# Copy_ofAirScout_SchematicsV2_0.net
KiCad netlist of a schematic drawn in Altium Designer
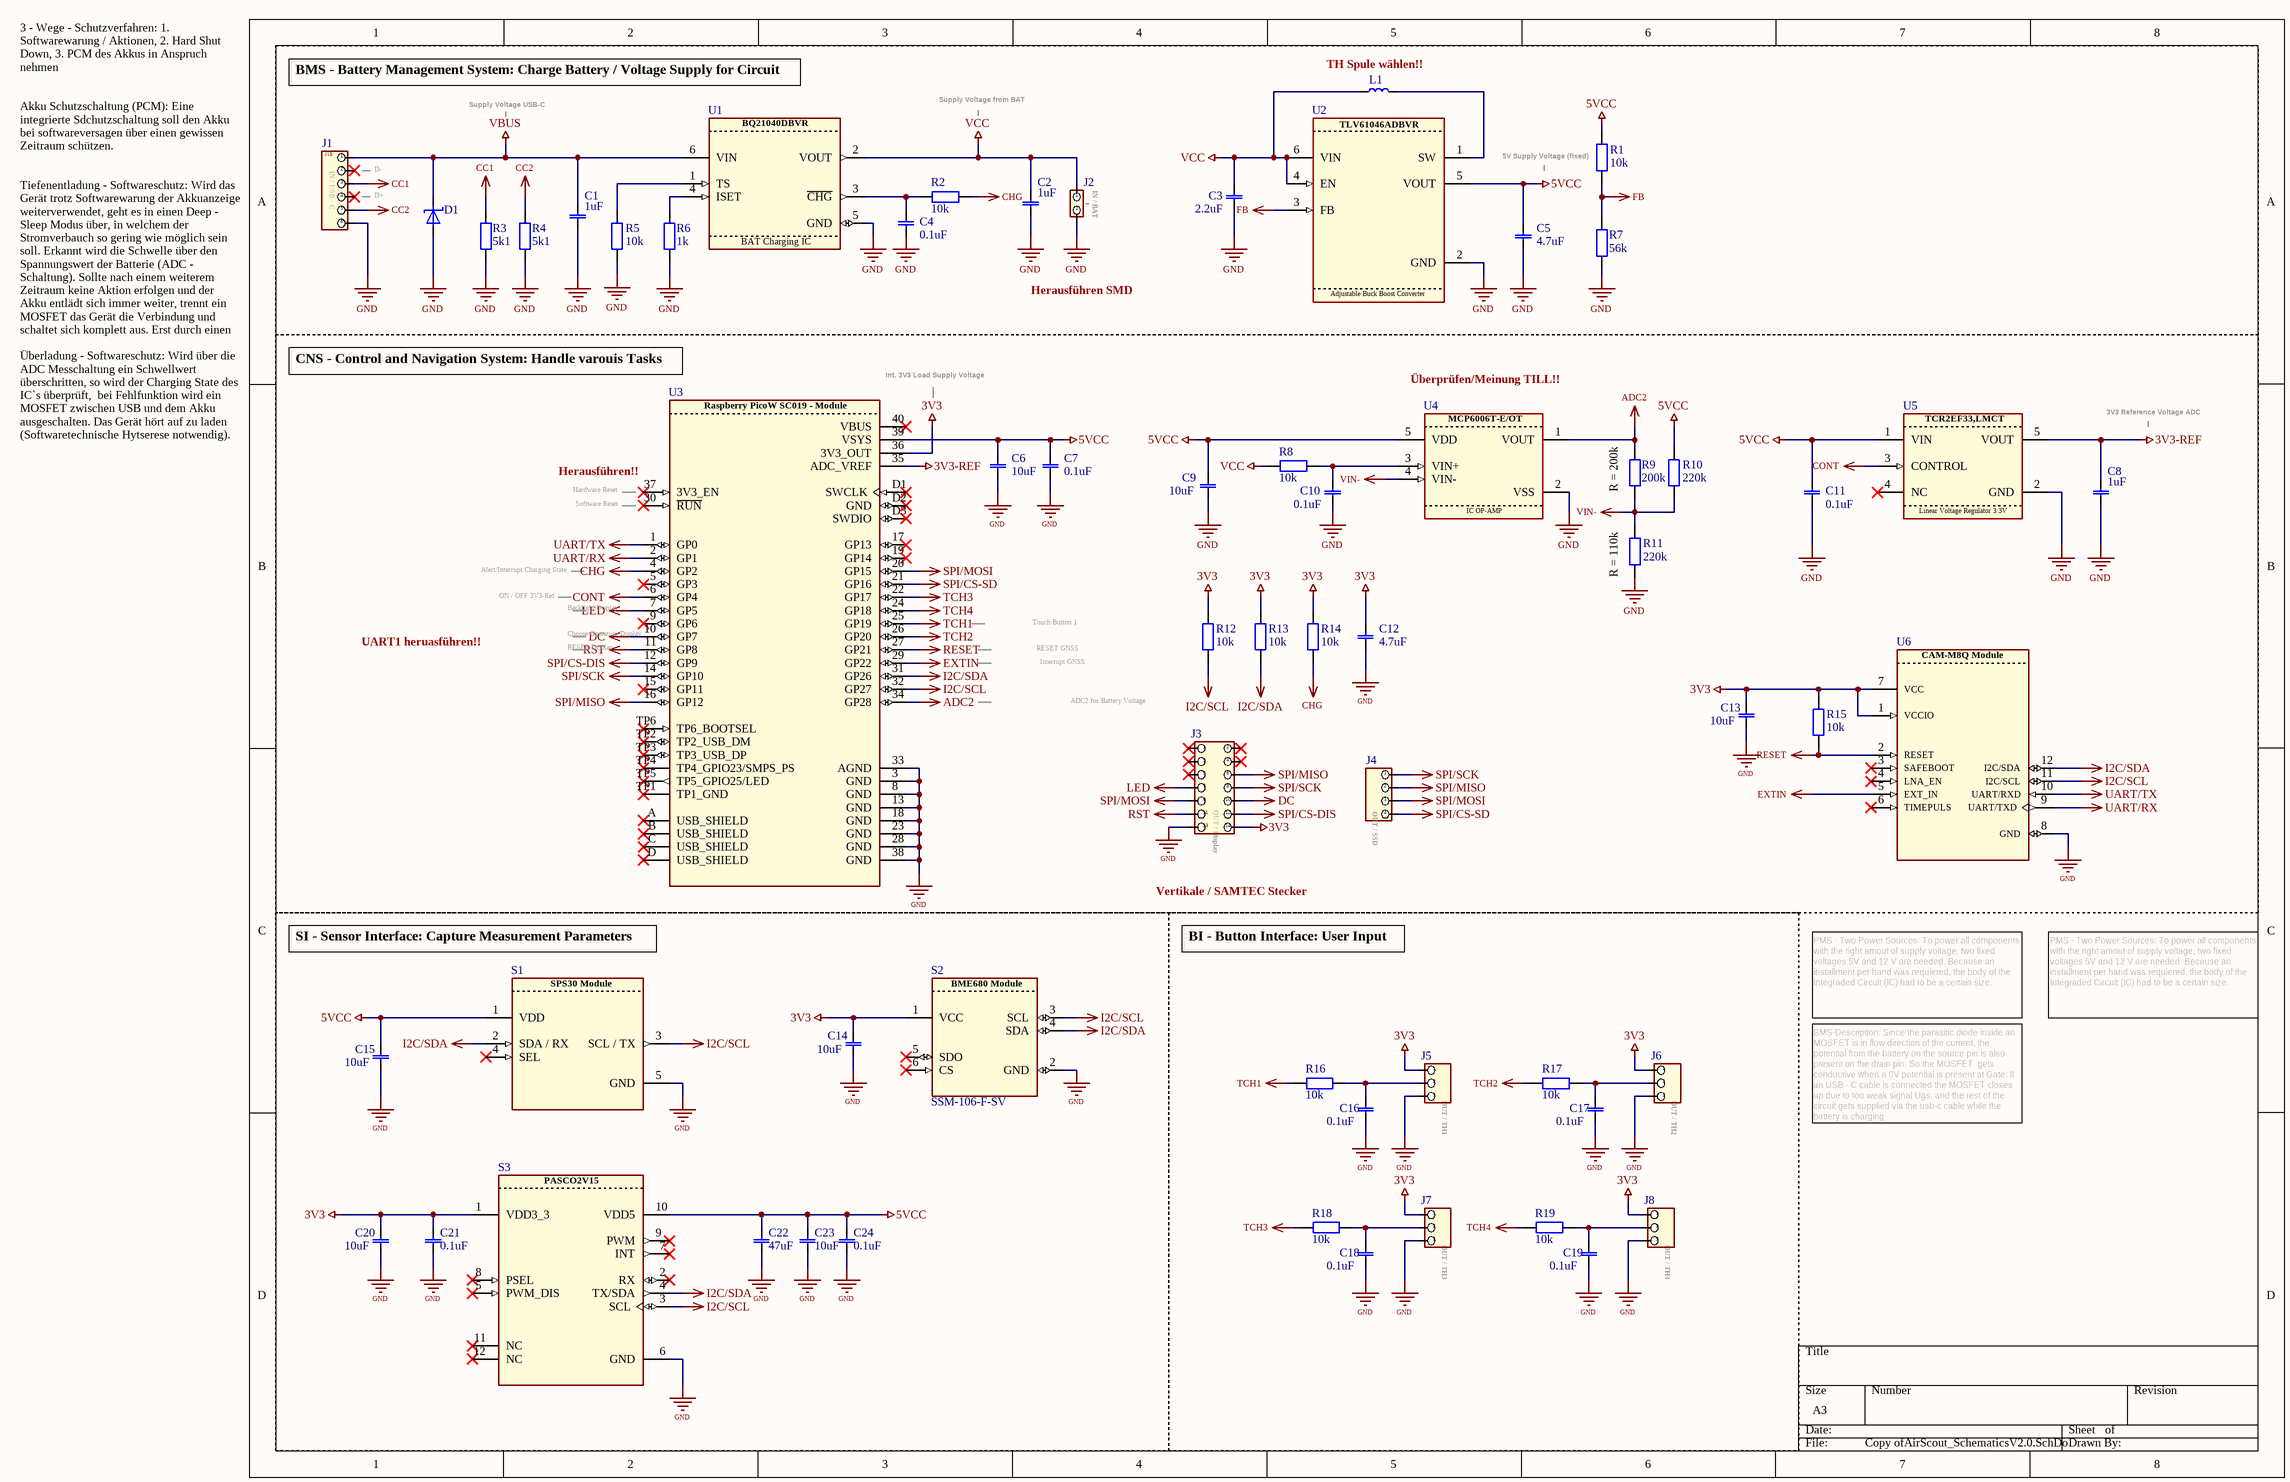
[diagram p0: Copy ofAirScout_SchematicsV2.0.SchDoc]

(export (version "E")
  (design (tool "Eeschema 10.0.6"))
  (components
    (comp (ref "C1")
      (value "1uF")
      (footprint "CAPC340180_140N_KEM")
      (description "CAP CER 1UF 25V X7R 1206")
      (fields (field (name "Comment") "C1206C105K3RACTU"))
      (libsource (lib "AirScoutSchLibV2.0") (part "CAP"))
    )
    (comp (ref "C2")
      (value "1uF")
      (footprint "CAPC340180_140N_KEM")
      (description "CAP CER 1UF 25V X7R 1206")
      (fields (field (name "Comment") "C1206C105K3RACTU"))
      (libsource (lib "AirScoutSchLibV2.0") (part "CAP"))
    )
    (comp (ref "C3")
      (value "2.2uF")
      (footprint "CAPC340180_140N_KEM")
      (description "CAP CER 2.2UF 50V X7R 1206")
      (fields (field (name "Comment") "CL31B225KBHNNNE"))
      (libsource (lib "AirScoutSchLibV2.0") (part "CAP"))
    )
    (comp (ref "C4")
      (value "0.1uF")
      (footprint "CAPC340180_140N_KEM")
      (description "CAP CER 0.1UF 50V X7R 1206")
      (fields (field (name "Comment") "C1206C104K5RACTU"))
      (libsource (lib "AirScoutSchLibV2.0") (part "CAP"))
    )
    (comp (ref "C5")
      (value "4.7uF")
      (footprint "CAPC340180_140N_KEM")
      (description "CAP CER 4.7UF 50V X7R 1206")
      (fields (field (name "Comment") "CL31B475KBHNFNE"))
      (libsource (lib "AirScoutSchLibV2.0") (part "CAP"))
    )
    (comp (ref "C6")
      (value "10uF")
      (footprint "CAPC340180_140N_KEM")
      (description "CAP CER 10UF 25V X7R 1206")
      (fields (field (name "Comment") "CL31B106KAHNNNE"))
      (libsource (lib "AirScoutSchLibV2.0") (part "CAP"))
    )
    (comp (ref "C7")
      (value "0.1uF")
      (footprint "CAPC340180_140N_KEM")
      (description "CAP CER 0.1UF 50V X7R 1206")
      (fields (field (name "Comment") "C1206C104K5RACTU"))
      (libsource (lib "AirScoutSchLibV2.0") (part "CAP"))
    )
    (comp (ref "C8")
      (value "1uF")
      (footprint "CAPC340180_140N_KEM")
      (description "CAP CER 1UF 25V X7R 1206")
      (fields (field (name "Comment") "C1206C105K3RACTU"))
      (libsource (lib "AirScoutSchLibV2.0") (part "CAP"))
    )
    (comp (ref "C9")
      (value "10uF")
      (footprint "CAPC340180_140N_KEM")
      (description "CAP CER 10UF 25V X7R 1206")
      (fields (field (name "Comment") "CL31B106KAHNNNE"))
      (libsource (lib "AirScoutSchLibV2.0") (part "CAP"))
    )
    (comp (ref "C10")
      (value "0.1uF")
      (footprint "CAPC340180_140N_KEM")
      (description "CAP CER 0.1UF 50V X7R 1206")
      (fields (field (name "Comment") "C1206C104K5RACTU"))
      (libsource (lib "AirScoutSchLibV2.0") (part "CAP"))
    )
    (comp (ref "C11")
      (value "0.1uF")
      (footprint "CAPC340180_140N_KEM")
      (description "CAP CER 0.1UF 50V X7R 1206")
      (fields (field (name "Comment") "C1206C104K5RACTU"))
      (libsource (lib "AirScoutSchLibV2.0") (part "CAP"))
    )
    (comp (ref "C12")
      (value "4.7uF")
      (footprint "CAPC340180_140N_KEM")
      (description "CAP CER 4.7UF 50V X7R 1206")
      (fields (field (name "Comment") "CL31B475KBHNFNE"))
      (libsource (lib "AirScoutSchLibV2.0") (part "CAP"))
    )
    (comp (ref "C13")
      (value "10uF")
      (footprint "CAPC340180_140N_KEM")
      (description "CAP CER 10UF 25V X7R 1206")
      (fields (field (name "Comment") "CL31B106KAHNNNE"))
      (libsource (lib "AirScoutSchLibV2.0") (part "CAP"))
    )
    (comp (ref "C14")
      (value "10uF")
      (footprint "CAPC340180_140N_KEM")
      (description "CAP CER 10UF 25V X7R 1206")
      (fields (field (name "Comment") "CL31B106KAHNNNE"))
      (libsource (lib "AirScoutSchLibV2.0") (part "CAP"))
    )
    (comp (ref "C15")
      (value "10uF")
      (footprint "CAPC340180_140N_KEM")
      (description "CAP CER 10UF 25V X7R 1206")
      (fields (field (name "Comment") "CL31B106KAHNNNE"))
      (libsource (lib "AirScoutSchLibV2.0") (part "CAP"))
    )
    (comp (ref "C16")
      (value "0.1uF")
      (footprint "CAPC340180_140N_KEM")
      (description "CAP CER 0.1UF 50V X7R 1206")
      (fields (field (name "Comment") "C1206C104K5RACTU"))
      (libsource (lib "AirScoutSchLibV2.0") (part "CAP"))
    )
    (comp (ref "C17")
      (value "0.1uF")
      (footprint "CAPC340180_140N_KEM")
      (description "CAP CER 0.1UF 50V X7R 1206")
      (fields (field (name "Comment") "C1206C104K5RACTU"))
      (libsource (lib "AirScoutSchLibV2.0") (part "CAP"))
    )
    (comp (ref "C18")
      (value "0.1uF")
      (footprint "CAPC340180_140N_KEM")
      (description "CAP CER 0.1UF 50V X7R 1206")
      (fields (field (name "Comment") "C1206C104K5RACTU"))
      (libsource (lib "AirScoutSchLibV2.0") (part "CAP"))
    )
    (comp (ref "C19")
      (value "0.1uF")
      (footprint "CAPC340180_140N_KEM")
      (description "CAP CER 0.1UF 50V X7R 1206")
      (fields (field (name "Comment") "C1206C104K5RACTU"))
      (libsource (lib "AirScoutSchLibV2.0") (part "CAP"))
    )
    (comp (ref "C20")
      (value "10uF")
      (footprint "CAPC340180_140N_KEM")
      (description "CAP CER 10UF 25V X7R 1206")
      (fields (field (name "Comment") "CL31B106KAHNNNE"))
      (libsource (lib "AirScoutSchLibV2.0") (part "CAP"))
    )
    (comp (ref "C21")
      (value "0.1uF")
      (footprint "CAPC340180_140N_KEM")
      (description "CAP CER 0.1UF 50V X7R 1206")
      (fields (field (name "Comment") "C1206C104K5RACTU"))
      (libsource (lib "AirScoutSchLibV2.0") (part "CAP"))
    )
    (comp (ref "C22")
      (value "47uF")
      (footprint "CAPC340180_140N_KEM")
      (description "CAP CER 47UF 6.3V X5R 1206")
      (fields (field (name "Comment") "CL31A476MQHNNNE"))
      (libsource (lib "AirScoutSchLibV2.0") (part "CAP"))
    )
    (comp (ref "C23")
      (value "10uF")
      (footprint "CAPC340180_140N_KEM")
      (description "CAP CER 10UF 25V X7R 1206")
      (fields (field (name "Comment") "CL31B106KAHNNNE"))
      (libsource (lib "AirScoutSchLibV2.0") (part "CAP"))
    )
    (comp (ref "C24")
      (value "0.1uF")
      (footprint "CAPC340180_140N_KEM")
      (description "CAP CER 0.1UF 50V X7R 1206")
      (fields (field (name "Comment") "C1206C104K5RACTU"))
      (libsource (lib "AirScoutSchLibV2.0") (part "CAP"))
    )
    (comp (ref "D1")
      (value "SMBJ14CA-13-F")
      (footprint "SMB_DIO")
      (description "TVS DIODE 14VWM 23.2VC SMB")
      (libsource (lib "AirScoutSchLibV2.0") (part "Diode-Schottky"))
    )
    (comp (ref "J1")
      (value "B6B-PH-K-S")
      (footprint "JST_B6B-PH-K-S")
      (description "CONN HEADER VERT 6POS 2MM")
      (libsource (lib "AirScoutSchLibV2.0") (part "CON6x1"))
    )
    (comp (ref "J2")
      (value "B02B-PASK-1")
      (footprint "JST_B2B-PH-K-S")
      (description "CONN HEADER VERT 2POS 2MM")
      (libsource (lib "AirScoutSchLibV2.0") (part "CON2x1_vertical"))
    )
    (comp (ref "J3")
      (value "0705430013")
      (footprint "CONN_14POL_SAMTEC")
      (description "CONN HEADER VERT 14POS 2.54MM")
      (libsource (lib "AirScoutSchLibV2.0") (part "CON7x2"))
    )
    (comp (ref "J4")
      (value "4x1 vertical Connector Box")
      (footprint "JST_B4B-XH-A")
      (description "Can be used to create connectivity between two plates with cables or similar.")
      (libsource (lib "AirScoutSchLibV2.0") (part "CON 4x1"))
    )
    (comp (ref "J5")
      (value "0705430002")
      (footprint "CONN_3POL_SAMTEC")
      (description "CONN HEADER VERT 3POS 2.54MM")
      (libsource (lib "AirScoutSchLibV2.0") (part "CON 3x1"))
    )
    (comp (ref "J6")
      (value "0705430002")
      (footprint "CONN_3POL_SAMTEC")
      (description "CONN HEADER VERT 3POS 2.54MM")
      (libsource (lib "AirScoutSchLibV2.0") (part "CON 3x1"))
    )
    (comp (ref "J7")
      (value "0705430002")
      (footprint "CONN_3POL_SAMTEC")
      (description "CONN HEADER VERT 3POS 2.54MM")
      (libsource (lib "AirScoutSchLibV2.0") (part "CON 3x1"))
    )
    (comp (ref "J8")
      (value "0705430002")
      (footprint "CONN_3POL_SAMTEC")
      (description "CONN HEADER VERT 3POS 2.54MM")
      (libsource (lib "AirScoutSchLibV2.0") (part "CON 3x1"))
    )
    (comp (ref "L1")
      (value "PA4332.103NLT")
      (footprint "IND_FDSD0420-H-100M=P3")
      (description "FIXED IND 10UH 2A 216 MOHM SMD; \r\nAIUR-05-100K")
      (libsource (lib "AirScoutSchLibV2.0") (part "Inductor"))
    )
    (comp (ref "R1")
      (value "10k")
      (footprint "RESC3116X65N")
      (description "RES 10K OHM 1% 1/4W 1206")
      (fields (field (name "Comment") "RC1206FR-0710KL"))
      (libsource (lib "AirScoutSchLibV2.0") (part "RES"))
    )
    (comp (ref "R2")
      (value "10k")
      (footprint "RESC3116X65N")
      (description "RES 10K OHM 1% 1/4W 1206")
      (fields (field (name "Comment") "RC1206FR-0710KL"))
      (libsource (lib "AirScoutSchLibV2.0") (part "RES"))
    )
    (comp (ref "R3")
      (value "5k1")
      (footprint "RESC3116X65N")
      (description "RES 5.1K OHM 5% 1/4W 1206")
      (fields (field (name "Comment") "RMCF1206JT5K10"))
      (libsource (lib "AirScoutSchLibV2.0") (part "RES"))
    )
    (comp (ref "R4")
      (value "5k1")
      (footprint "RESC3116X65N")
      (description "RES 5.1K OHM 5% 1/4W 1206")
      (fields (field (name "Comment") "RMCF1206JT5K10"))
      (libsource (lib "AirScoutSchLibV2.0") (part "RES"))
    )
    (comp (ref "R5")
      (value "10k")
      (footprint "RESC3116X65N")
      (description "RES 10K OHM 1% 1/4W 1206")
      (fields (field (name "Comment") "RC1206FR-0710KL"))
      (libsource (lib "AirScoutSchLibV2.0") (part "RES"))
    )
    (comp (ref "R6")
      (value "1k")
      (footprint "RESC3116X65N")
      (description "RES 1K OHM 1% 1/2W 1206")
      (fields (field (name "Comment") "RNCP1206FTD1K00"))
      (libsource (lib "AirScoutSchLibV2.0") (part "RES"))
    )
    (comp (ref "R7")
      (value "56k")
      (footprint "RESC3116X65N")
      (description "RES 56K OHM 5% 1/4W 1206")
      (fields (field (name "Comment") "RMCF1206JT56K0"))
      (libsource (lib "AirScoutSchLibV2.0") (part "RES"))
    )
    (comp (ref "R8")
      (value "10k")
      (footprint "RESC3116X65N")
      (description "RES 10K OHM 1% 1/4W 1206")
      (fields (field (name "Comment") "RC1206FR-0710KL"))
      (libsource (lib "AirScoutSchLibV2.0") (part "RES"))
    )
    (comp (ref "R9")
      (value "200k")
      (footprint "RESC3116X65N")
      (description "RES 200K OHM 5% 1/4W 1206")
      (fields (field (name "Comment") "RC1206JR-07200KL"))
      (libsource (lib "AirScoutSchLibV2.0") (part "RES"))
    )
    (comp (ref "R10")
      (value "220k")
      (footprint "RESC3116X65N")
      (description "RES 220K OHM 5% 1/4W 1206")
      (fields (field (name "Comment") "RC1206JR-07220KL"))
      (libsource (lib "AirScoutSchLibV2.0") (part "RES"))
    )
    (comp (ref "R11")
      (value "220k")
      (footprint "RESC3116X65N")
      (description "RES 220K OHM 5% 1/4W 1206")
      (fields (field (name "Comment") "RC1206JR-07220KL"))
      (libsource (lib "AirScoutSchLibV2.0") (part "RES"))
    )
    (comp (ref "R12")
      (value "10k")
      (footprint "RESC3116X65N")
      (description "RES 10K OHM 1% 1/4W 1206")
      (fields (field (name "Comment") "RC1206FR-0710KL"))
      (libsource (lib "AirScoutSchLibV2.0") (part "RES"))
    )
    (comp (ref "R13")
      (value "10k")
      (footprint "RESC3116X65N")
      (description "RES 10K OHM 1% 1/4W 1206")
      (fields (field (name "Comment") "RC1206FR-0710KL"))
      (libsource (lib "AirScoutSchLibV2.0") (part "RES"))
    )
    (comp (ref "R14")
      (value "10k")
      (footprint "RESC3116X65N")
      (description "RES 10K OHM 1% 1/4W 1206")
      (fields (field (name "Comment") "RC1206FR-0710KL"))
      (libsource (lib "AirScoutSchLibV2.0") (part "RES"))
    )
    (comp (ref "R15")
      (value "10k")
      (footprint "RESC3116X65N")
      (description "RES 10K OHM 1% 1/4W 1206")
      (fields (field (name "Comment") "RC1206FR-0710KL"))
      (libsource (lib "AirScoutSchLibV2.0") (part "RES"))
    )
    (comp (ref "R16")
      (value "10k")
      (footprint "RESC3116X65N")
      (description "RES 10K OHM 1% 1/4W 1206")
      (fields (field (name "Comment") "RC1206FR-0710KL"))
      (libsource (lib "AirScoutSchLibV2.0") (part "RES"))
    )
    (comp (ref "R17")
      (value "10k")
      (footprint "RESC3116X65N")
      (description "RES 10K OHM 1% 1/4W 1206")
      (fields (field (name "Comment") "RC1206FR-0710KL"))
      (libsource (lib "AirScoutSchLibV2.0") (part "RES"))
    )
    (comp (ref "R18")
      (value "10k")
      (footprint "RESC3116X65N")
      (description "RES 10K OHM 1% 1/4W 1206")
      (fields (field (name "Comment") "RC1206FR-0710KL"))
      (libsource (lib "AirScoutSchLibV2.0") (part "RES"))
    )
    (comp (ref "R19")
      (value "10k")
      (footprint "RESC3116X65N")
      (description "RES 10K OHM 1% 1/4W 1206")
      (fields (field (name "Comment") "RC1206FR-0710KL"))
      (libsource (lib "AirScoutSchLibV2.0") (part "RES"))
    )
    (comp (ref "S1")
      (value "B5B-ZR")
      (footprint "CONN5_B5B-ZR_JST")
      (description "Plug: CONN HEADER VERT 5POS 1.5MM; Air Sensor Dust Sensor Box SPS30 Module: 1649-1106-ND")
      (libsource (lib "AirScoutSchLibV2.0") (part "SPS30 Module"))
    )
    (comp (ref "S2")
      (value "SSM-106-F-SV")
      (footprint "PIM357")
      (libsource (lib "AirScoutSchLibV2.0") (part "BME680 Module"))
    )
    (comp (ref "S3")
      (value "SSM-106-F-SV")
      (footprint "IFX-SMD-LG-MLGA-14-1-V_MODUL")
      (description "(2x) CONN RCPT 6POS 0.1 GOLD SMD; Sensor: EVALCO25VMINIBOARDTOBO1; EVAL BOARD")
      (libsource (lib "AirScoutSchLibV2.0") (part "PASCO2V15 Module"))
    )
    (comp (ref "U1")
      (value "BQ21040DBVR")
      (footprint "SOT95P280X145-6N")
      (fields (field (name "MF") "Texas Instruments"))
      (libsource (lib "AirScoutSchLibV2.0") (part "BQ21040DBVR"))
    )
    (comp (ref "U2")
      (value "TLV61046ADBVR")
      (footprint "DBV0006A_M")
      (description "28-V Output Voltage Boost Converter with Power Diode and Isolation Switch 6-SOT-23 -40 to 125")
      (fields (field (name "COPYRIGHT") "Copyright (C) 2025 Ultra Librarian. All rights reserved."))
      (libsource (lib "AirScoutSchLibV2.0") (part "TLV61046ADBVR"))
    )
    (comp (ref "U3")
      (value "SSM-120-L-SV-BE-K-TR")
      (footprint "PicoW SC019")
      (description "(2x) CONN RCPT 20POS 0.1 GOLD SMD; PicoW: SC0918; RASPBERRY PI PICO W RP2040")
      (libsource (lib "AirScoutSchLibV2.0") (part "Raspberry PicoW SC019 Module"))
    )
    (comp (ref "U4")
      (value "MCP6006T-E/OT")
      (footprint "SOT23-5-AP2202K_DIO-M")
      (description "IC OPAMP GP 1 CIRCUIT SOT23-5")
      (libsource (lib "AirScoutSchLibV2.0") (part "MCP6006T-E/OT"))
    )
    (comp (ref "U5")
      (value "TCR2EF33,LM(CT")
      (footprint "SOT-25   SMV_TOS")
      (description "IC REG LINEAR 3.3V 200MA SMV")
      (fields (field (name "COPYRIGHT") "Copyright (C) 2025 Ultra Librarian. All rights reserved."))
      (libsource (lib "AirScoutSchLibV2.0") (part "TCR2EF33,LMCT"))
    )
    (comp (ref "U6")
      (value "FM20206VBNN; SSM-106-F-SV")
      (footprint "CAM8MQ-Mod")
      (description "(2x) RECEPTACLE, SMT, SINGLE ROW, .10; GPS - Module:  201880; CAM-M8Q-BREAKOUT MULTI GNSS MODU")
      (libsource (lib "AirScoutSchLibV2.0") (part "CAM-M8Q Module"))
    )
  )
  (nets
    (net (code "1") (name "3V3") (class "Default")
      (node (ref "C12") (pin "2") (pinfunction "2_2") (pintype "passive"))
      (node (ref "C13") (pin "2") (pinfunction "2_2") (pintype "passive"))
      (node (ref "C14") (pin "2") (pinfunction "2_2") (pintype "passive"))
      (node (ref "C20") (pin "2") (pinfunction "2_2") (pintype "passive"))
      (node (ref "C21") (pin "2") (pinfunction "2_2") (pintype "passive"))
      (node (ref "J3") (pin "14") (pinfunction "14_14") (pintype "passive"))
      (node (ref "J5") (pin "1") (pinfunction "1_1") (pintype "passive"))
      (node (ref "J6") (pin "1") (pinfunction "1_1") (pintype "passive"))
      (node (ref "J7") (pin "1") (pinfunction "1_1") (pintype "passive"))
      (node (ref "J8") (pin "1") (pinfunction "1_1") (pintype "passive"))
      (node (ref "R12") (pin "2") (pinfunction "2_2") (pintype "passive"))
      (node (ref "R13") (pin "2") (pinfunction "2_2") (pintype "passive"))
      (node (ref "R14") (pin "2") (pinfunction "2_2") (pintype "passive"))
      (node (ref "R15") (pin "2") (pinfunction "2_2") (pintype "passive"))
      (node (ref "S2") (pin "1") (pinfunction "VCC_1") (pintype "power_in"))
      (node (ref "S3") (pin "1") (pinfunction "VDD3_3_1") (pintype "power_in"))
      (node (ref "U3") (pin "36") (pinfunction "3V3_OUT_36") (pintype "power_in"))
      (node (ref "U6") (pin "1") (pinfunction "VCCIO_1") (pintype "input"))
      (node (ref "U6") (pin "7") (pinfunction "VCC_7") (pintype "power_in"))
    )
    (net (code "2") (name "3V3-REF") (class "Default")
      (node (ref "C8") (pin "2") (pinfunction "2_2") (pintype "passive"))
      (node (ref "U3") (pin "35") (pinfunction "ADC_VREF_35") (pintype "power_in"))
      (node (ref "U5") (pin "5") (pinfunction "VOUT_5") (pintype "power_in"))
    )
    (net (code "3") (name "5VCC") (class "Default")
      (node (ref "C11") (pin "2") (pinfunction "2_2") (pintype "passive"))
      (node (ref "C15") (pin "2") (pinfunction "2_2") (pintype "passive"))
      (node (ref "C22") (pin "2") (pinfunction "2_2") (pintype "passive"))
      (node (ref "C23") (pin "2") (pinfunction "2_2") (pintype "passive"))
      (node (ref "C24") (pin "2") (pinfunction "2_2") (pintype "passive"))
      (node (ref "C5") (pin "2") (pinfunction "2_2") (pintype "passive"))
      (node (ref "C6") (pin "2") (pinfunction "2_2") (pintype "passive"))
      (node (ref "C7") (pin "2") (pinfunction "2_2") (pintype "passive"))
      (node (ref "C9") (pin "2") (pinfunction "2_2") (pintype "passive"))
      (node (ref "R1") (pin "2") (pinfunction "2_2") (pintype "passive"))
      (node (ref "R10") (pin "2") (pinfunction "2_2") (pintype "passive"))
      (node (ref "S1") (pin "1") (pinfunction "VDD_1") (pintype "passive"))
      (node (ref "S3") (pin "10") (pinfunction "VDD5_10") (pintype "power_in"))
      (node (ref "U2") (pin "5") (pinfunction "VOUT_5") (pintype "power_in"))
      (node (ref "U3") (pin "39") (pinfunction "VSYS_39") (pintype "power_in"))
      (node (ref "U4") (pin "5") (pinfunction "VDD_5") (pintype "power_in"))
      (node (ref "U5") (pin "1") (pinfunction "VIN_1") (pintype "power_in"))
    )
    (net (code "4") (name "ADC2") (class "Default")
      (node (ref "R9") (pin "2") (pinfunction "2_2") (pintype "passive"))
      (node (ref "U3") (pin "34") (pinfunction "GP28_34") (pintype "bidirectional"))
      (node (ref "U4") (pin "1") (pinfunction "VOUT_1") (pintype "power_in"))
    )
    (net (code "5") (name "CC1") (class "Default")
      (node (ref "J1") (pin "3") (pinfunction "3_3") (pintype "passive"))
      (node (ref "R3") (pin "2") (pinfunction "2_2") (pintype "passive"))
    )
    (net (code "6") (name "CC2") (class "Default")
      (node (ref "J1") (pin "5") (pinfunction "5_5") (pintype "passive"))
      (node (ref "R4") (pin "2") (pinfunction "2_2") (pintype "passive"))
    )
    (net (code "7") (name "CHG") (class "Default")
      (node (ref "R14") (pin "1") (pinfunction "1_1") (pintype "passive"))
      (node (ref "R2") (pin "1") (pinfunction "1_1") (pintype "passive"))
      (node (ref "U3") (pin "4") (pinfunction "GP2_4") (pintype "bidirectional"))
    )
    (net (code "8") (name "CONT") (class "Default")
      (node (ref "U3") (pin "6") (pinfunction "GP4_6") (pintype "bidirectional"))
      (node (ref "U5") (pin "3") (pinfunction "CONTROL_3") (pintype "input"))
    )
    (net (code "9") (name "DC") (class "Default")
      (node (ref "J3") (pin "10") (pinfunction "10_10") (pintype "passive"))
      (node (ref "U3") (pin "10") (pinfunction "GP7_10") (pintype "bidirectional"))
    )
    (net (code "10") (name "EXTIN") (class "Default")
      (node (ref "U3") (pin "29") (pinfunction "GP22_29") (pintype "bidirectional"))
      (node (ref "U6") (pin "5") (pinfunction "EXT_IN_5") (pintype "input"))
    )
    (net (code "11") (name "FB") (class "Default")
      (node (ref "R1") (pin "1") (pinfunction "1_1") (pintype "passive"))
      (node (ref "R7") (pin "2") (pinfunction "2_2") (pintype "passive"))
      (node (ref "U2") (pin "3") (pinfunction "FB_3") (pintype "input"))
    )
    (net (code "12") (name "GND") (class "Default")
      (node (ref "C1") (pin "1") (pinfunction "1_1") (pintype "passive"))
      (node (ref "C10") (pin "1") (pinfunction "1_1") (pintype "passive"))
      (node (ref "C11") (pin "1") (pinfunction "1_1") (pintype "passive"))
      (node (ref "C12") (pin "1") (pinfunction "1_1") (pintype "passive"))
      (node (ref "C13") (pin "1") (pinfunction "1_1") (pintype "passive"))
      (node (ref "C14") (pin "1") (pinfunction "1_1") (pintype "passive"))
      (node (ref "C15") (pin "1") (pinfunction "1_1") (pintype "passive"))
      (node (ref "C16") (pin "1") (pinfunction "1_1") (pintype "passive"))
      (node (ref "C17") (pin "1") (pinfunction "1_1") (pintype "passive"))
      (node (ref "C18") (pin "1") (pinfunction "1_1") (pintype "passive"))
      (node (ref "C19") (pin "1") (pinfunction "1_1") (pintype "passive"))
      (node (ref "C2") (pin "1") (pinfunction "1_1") (pintype "passive"))
      (node (ref "C20") (pin "1") (pinfunction "1_1") (pintype "passive"))
      (node (ref "C21") (pin "1") (pinfunction "1_1") (pintype "passive"))
      (node (ref "C22") (pin "1") (pinfunction "1_1") (pintype "passive"))
      (node (ref "C23") (pin "1") (pinfunction "1_1") (pintype "passive"))
      (node (ref "C24") (pin "1") (pinfunction "1_1") (pintype "passive"))
      (node (ref "C3") (pin "1") (pinfunction "1_1") (pintype "passive"))
      (node (ref "C4") (pin "1") (pinfunction "1_1") (pintype "passive"))
      (node (ref "C5") (pin "1") (pinfunction "1_1") (pintype "passive"))
      (node (ref "C6") (pin "1") (pinfunction "1_1") (pintype "passive"))
      (node (ref "C7") (pin "1") (pinfunction "1_1") (pintype "passive"))
      (node (ref "C8") (pin "1") (pinfunction "1_1") (pintype "passive"))
      (node (ref "C9") (pin "1") (pinfunction "1_1") (pintype "passive"))
      (node (ref "D1") (pin "A") (pinfunction "A_A") (pintype "passive"))
      (node (ref "J1") (pin "6") (pinfunction "6_6") (pintype "passive"))
      (node (ref "J2") (pin "2") (pinfunction "-_2") (pintype "passive"))
      (node (ref "J3") (pin "13") (pinfunction "13_13") (pintype "passive"))
      (node (ref "J5") (pin "3") (pinfunction "3_3") (pintype "passive"))
      (node (ref "J6") (pin "3") (pinfunction "3_3") (pintype "passive"))
      (node (ref "J7") (pin "3") (pinfunction "3_3") (pintype "passive"))
      (node (ref "J8") (pin "3") (pinfunction "3_3") (pintype "passive"))
      (node (ref "R11") (pin "1") (pinfunction "1_1") (pintype "passive"))
      (node (ref "R3") (pin "1") (pinfunction "1_1") (pintype "passive"))
      (node (ref "R4") (pin "1") (pinfunction "1_1") (pintype "passive"))
      (node (ref "R5") (pin "1") (pinfunction "1_1") (pintype "passive"))
      (node (ref "R6") (pin "1") (pinfunction "1_1") (pintype "passive"))
      (node (ref "R7") (pin "1") (pinfunction "1_1") (pintype "passive"))
      (node (ref "S1") (pin "5") (pinfunction "GND_5") (pintype "passive"))
      (node (ref "S2") (pin "2") (pinfunction "GND_2") (pintype "bidirectional"))
      (node (ref "S3") (pin "6") (pinfunction "GND_6") (pintype "power_in"))
      (node (ref "U1") (pin "5") (pinfunction "GND_5") (pintype "bidirectional"))
      (node (ref "U2") (pin "2") (pinfunction "GND_2") (pintype "power_in"))
      (node (ref "U3") (pin "13") (pinfunction "GND_13") (pintype "power_in"))
      (node (ref "U3") (pin "18") (pinfunction "GND_18") (pintype "power_in"))
      (node (ref "U3") (pin "23") (pinfunction "GND_23") (pintype "power_in"))
      (node (ref "U3") (pin "28") (pinfunction "GND_28") (pintype "power_in"))
      (node (ref "U3") (pin "3") (pinfunction "GND_3") (pintype "power_in"))
      (node (ref "U3") (pin "33") (pinfunction "AGND_33") (pintype "power_in"))
      (node (ref "U3") (pin "38") (pinfunction "GND_38") (pintype "power_in"))
      (node (ref "U3") (pin "8") (pinfunction "GND_8") (pintype "power_in"))
      (node (ref "U4") (pin "2") (pinfunction "VSS_2") (pintype "power_in"))
      (node (ref "U5") (pin "2") (pinfunction "GND_2") (pintype "power_in"))
      (node (ref "U6") (pin "8") (pinfunction "GND_8") (pintype "bidirectional"))
    )
    (net (code "13") (name "I2C{slash}SCL") (class "Default")
      (node (ref "R12") (pin "1") (pinfunction "1_1") (pintype "passive"))
      (node (ref "S1") (pin "3") (pinfunction "SCL_/_TX_3") (pintype "output"))
      (node (ref "S2") (pin "3") (pinfunction "SCL_3") (pintype "bidirectional"))
      (node (ref "S3") (pin "3") (pinfunction "SCL_3") (pintype "bidirectional"))
      (node (ref "U3") (pin "32") (pinfunction "GP27_32") (pintype "bidirectional"))
      (node (ref "U6") (pin "11") (pinfunction "I2C/SCL_11") (pintype "bidirectional"))
    )
    (net (code "14") (name "I2C{slash}SDA") (class "Default")
      (node (ref "R13") (pin "1") (pinfunction "1_1") (pintype "passive"))
      (node (ref "S1") (pin "2") (pinfunction "SDA_/_RX_2") (pintype "input"))
      (node (ref "S2") (pin "4") (pinfunction "SDA_4") (pintype "bidirectional"))
      (node (ref "S3") (pin "4") (pinfunction "TX/SDA_4") (pintype "output"))
      (node (ref "U3") (pin "31") (pinfunction "GP26_31") (pintype "bidirectional"))
      (node (ref "U6") (pin "12") (pinfunction "I2C/SDA_12") (pintype "bidirectional"))
    )
    (net (code "15") (name "LED") (class "Default")
      (node (ref "J3") (pin "7") (pinfunction "7_7") (pintype "passive"))
      (node (ref "U3") (pin "7") (pinfunction "GP5_7") (pintype "bidirectional"))
    )
    (net (code "16") (name "Net-(C16-Pad2)") (class "Default")
      (node (ref "C16") (pin "2") (pinfunction "2_2") (pintype "passive"))
      (node (ref "J5") (pin "2") (pinfunction "2_2") (pintype "passive"))
      (node (ref "R16") (pin "1") (pinfunction "1_1") (pintype "passive"))
    )
    (net (code "17") (name "Net-(C17-Pad2)") (class "Default")
      (node (ref "C17") (pin "2") (pinfunction "2_2") (pintype "passive"))
      (node (ref "J6") (pin "2") (pinfunction "2_2") (pintype "passive"))
      (node (ref "R17") (pin "1") (pinfunction "1_1") (pintype "passive"))
    )
    (net (code "18") (name "Net-(C18-Pad2)") (class "Default")
      (node (ref "C18") (pin "2") (pinfunction "2_2") (pintype "passive"))
      (node (ref "J7") (pin "2") (pinfunction "2_2") (pintype "passive"))
      (node (ref "R18") (pin "1") (pinfunction "1_1") (pintype "passive"))
    )
    (net (code "19") (name "Net-(C19-Pad2)") (class "Default")
      (node (ref "C19") (pin "2") (pinfunction "2_2") (pintype "passive"))
      (node (ref "J8") (pin "2") (pinfunction "2_2") (pintype "passive"))
      (node (ref "R19") (pin "1") (pinfunction "1_1") (pintype "passive"))
    )
    (net (code "20") (name "Net-(U1-ISET)") (class "Default")
      (node (ref "R6") (pin "2") (pinfunction "2_2") (pintype "passive"))
      (node (ref "U1") (pin "4") (pinfunction "ISET_4") (pintype "input"))
    )
    (net (code "21") (name "Net-(U1-TS)") (class "Default")
      (node (ref "R5") (pin "2") (pinfunction "2_2") (pintype "passive"))
      (node (ref "U1") (pin "1") (pinfunction "TS_1") (pintype "input"))
    )
    (net (code "22") (name "Net-(U1-~{CHG})") (class "Default")
      (node (ref "C4") (pin "2") (pinfunction "2_2") (pintype "passive"))
      (node (ref "R2") (pin "2") (pinfunction "2_2") (pintype "passive"))
      (node (ref "U1") (pin "3") (pinfunction "~{CHG}_3") (pintype "output"))
    )
    (net (code "23") (name "Net-(U2-SW)") (class "Default")
      (node (ref "L1") (pin "2") (pinfunction "2_2") (pintype "passive"))
      (node (ref "U2") (pin "1") (pinfunction "SW_1") (pintype "power_in"))
    )
    (net (code "24") (name "Net-(U4-VIN+)") (class "Default")
      (node (ref "C10") (pin "2") (pinfunction "2_2") (pintype "passive"))
      (node (ref "R8") (pin "1") (pinfunction "1_1") (pintype "passive"))
      (node (ref "U4") (pin "3") (pinfunction "VIN+_3") (pintype "input"))
    )
    (net (code "25") (name "RESET") (class "Default")
      (node (ref "R15") (pin "1") (pinfunction "1_1") (pintype "passive"))
      (node (ref "U3") (pin "27") (pinfunction "GP21_27") (pintype "bidirectional"))
      (node (ref "U6") (pin "2") (pinfunction "RESET_2") (pintype "input"))
    )
    (net (code "26") (name "RST") (class "Default")
      (node (ref "J3") (pin "11") (pinfunction "11_11") (pintype "passive"))
      (node (ref "U3") (pin "11") (pinfunction "GP8_11") (pintype "bidirectional"))
    )
    (net (code "27") (name "SPI{slash}CS-DIS") (class "Default")
      (node (ref "J3") (pin "12") (pinfunction "12_12") (pintype "passive"))
      (node (ref "U3") (pin "12") (pinfunction "GP9_12") (pintype "bidirectional"))
    )
    (net (code "28") (name "SPI{slash}CS-SD") (class "Default")
      (node (ref "J4") (pin "4") (pinfunction "4_4") (pintype "passive"))
      (node (ref "U3") (pin "21") (pinfunction "GP16_21") (pintype "bidirectional"))
    )
    (net (code "29") (name "SPI{slash}MISO") (class "Default")
      (node (ref "J3") (pin "6") (pinfunction "6_6") (pintype "passive"))
      (node (ref "J4") (pin "2") (pinfunction "2_2") (pintype "passive"))
      (node (ref "U3") (pin "16") (pinfunction "GP12_16") (pintype "bidirectional"))
    )
    (net (code "30") (name "SPI{slash}MOSI") (class "Default")
      (node (ref "J3") (pin "9") (pinfunction "9_9") (pintype "passive"))
      (node (ref "J4") (pin "3") (pinfunction "3_3") (pintype "passive"))
      (node (ref "U3") (pin "20") (pinfunction "GP15_20") (pintype "bidirectional"))
    )
    (net (code "31") (name "SPI{slash}SCK") (class "Default")
      (node (ref "J3") (pin "8") (pinfunction "8_8") (pintype "passive"))
      (node (ref "J4") (pin "1") (pinfunction "1_1") (pintype "passive"))
      (node (ref "U3") (pin "14") (pinfunction "GP10_14") (pintype "bidirectional"))
    )
    (net (code "32") (name "TCH1") (class "Default")
      (node (ref "R16") (pin "2") (pinfunction "2_2") (pintype "passive"))
      (node (ref "U3") (pin "25") (pinfunction "GP19_25") (pintype "bidirectional"))
    )
    (net (code "33") (name "TCH2") (class "Default")
      (node (ref "R17") (pin "2") (pinfunction "2_2") (pintype "passive"))
      (node (ref "U3") (pin "26") (pinfunction "GP20_26") (pintype "bidirectional"))
    )
    (net (code "34") (name "TCH3") (class "Default")
      (node (ref "R18") (pin "2") (pinfunction "2_2") (pintype "passive"))
      (node (ref "U3") (pin "22") (pinfunction "GP17_22") (pintype "bidirectional"))
    )
    (net (code "35") (name "TCH4") (class "Default")
      (node (ref "R19") (pin "2") (pinfunction "2_2") (pintype "passive"))
      (node (ref "U3") (pin "24") (pinfunction "GP18_24") (pintype "bidirectional"))
    )
    (net (code "36") (name "UART{slash}RX") (class "Default")
      (node (ref "U3") (pin "2") (pinfunction "GP1_2") (pintype "bidirectional"))
      (node (ref "U6") (pin "9") (pinfunction "UART/TXD_9") (pintype "output"))
    )
    (net (code "37") (name "UART{slash}TX") (class "Default")
      (node (ref "U3") (pin "1") (pinfunction "GP0_1") (pintype "bidirectional"))
      (node (ref "U6") (pin "10") (pinfunction "UART/RXD_10") (pintype "input"))
    )
    (net (code "38") (name "VBUS") (class "Default")
      (node (ref "C1") (pin "2") (pinfunction "2_2") (pintype "passive"))
      (node (ref "D1") (pin "K") (pinfunction "K_K") (pintype "passive"))
      (node (ref "J1") (pin "1") (pinfunction "1_1") (pintype "passive"))
      (node (ref "U1") (pin "6") (pinfunction "VIN_6") (pintype "power_in"))
    )
    (net (code "39") (name "VCC") (class "Default")
      (node (ref "C2") (pin "2") (pinfunction "2_2") (pintype "passive"))
      (node (ref "C3") (pin "2") (pinfunction "2_2") (pintype "passive"))
      (node (ref "J2") (pin "1") (pinfunction "+_1") (pintype "passive"))
      (node (ref "L1") (pin "1") (pinfunction "1_1") (pintype "passive"))
      (node (ref "R8") (pin "2") (pinfunction "2_2") (pintype "passive"))
      (node (ref "U1") (pin "2") (pinfunction "VOUT_2") (pintype "output"))
      (node (ref "U2") (pin "4") (pinfunction "EN_4") (pintype "input"))
      (node (ref "U2") (pin "6") (pinfunction "VIN_6") (pintype "power_in"))
    )
    (net (code "40") (name "VIN-") (class "Default")
      (node (ref "R10") (pin "1") (pinfunction "1_1") (pintype "passive"))
      (node (ref "R11") (pin "2") (pinfunction "2_2") (pintype "passive"))
      (node (ref "R9") (pin "1") (pinfunction "1_1") (pintype "passive"))
      (node (ref "U4") (pin "4") (pinfunction "VIN-_4") (pintype "input"))
    )
    (net (code "41") (name "unconnected-(J1-Pad2)") (class "Default")
      (node (ref "J1") (pin "2") (pinfunction "2_2") (pintype "passive+no_connect"))
    )
    (net (code "42") (name "unconnected-(J1-Pad4)") (class "Default")
      (node (ref "J1") (pin "4") (pinfunction "4_4") (pintype "passive+no_connect"))
    )
    (net (code "43") (name "unconnected-(J3-Pad1)") (class "Default")
      (node (ref "J3") (pin "1") (pinfunction "1_1") (pintype "passive+no_connect"))
    )
    (net (code "44") (name "unconnected-(J3-Pad2)") (class "Default")
      (node (ref "J3") (pin "2") (pinfunction "2_2") (pintype "passive+no_connect"))
    )
    (net (code "45") (name "unconnected-(J3-Pad3)") (class "Default")
      (node (ref "J3") (pin "3") (pinfunction "3_3") (pintype "passive+no_connect"))
    )
    (net (code "46") (name "unconnected-(J3-Pad4)") (class "Default")
      (node (ref "J3") (pin "4") (pinfunction "4_4") (pintype "passive+no_connect"))
    )
    (net (code "47") (name "unconnected-(J3-Pad5)") (class "Default")
      (node (ref "J3") (pin "5") (pinfunction "5_5") (pintype "passive+no_connect"))
    )
    (net (code "48") (name "unconnected-(S1-SEL-Pad4)") (class "Default")
      (node (ref "S1") (pin "4") (pinfunction "SEL_4") (pintype "input+no_connect"))
    )
    (net (code "49") (name "unconnected-(S2-CS-Pad6)") (class "Default")
      (node (ref "S2") (pin "6") (pinfunction "CS_6") (pintype "input+no_connect"))
    )
    (net (code "50") (name "unconnected-(S2-SDO-Pad5)") (class "Default")
      (node (ref "S2") (pin "5") (pinfunction "SDO_5") (pintype "bidirectional+no_connect"))
    )
    (net (code "51") (name "unconnected-(S3-INT-Pad7)") (class "Default")
      (node (ref "S3") (pin "7") (pinfunction "INT_7") (pintype "output+no_connect"))
    )
    (net (code "52") (name "unconnected-(S3-NC-Pad11)") (class "Default")
      (node (ref "S3") (pin "11") (pinfunction "NC_11") (pintype "power_in+no_connect"))
    )
    (net (code "53") (name "unconnected-(S3-NC-Pad12)") (class "Default")
      (node (ref "S3") (pin "12") (pinfunction "NC_12") (pintype "passive+no_connect"))
    )
    (net (code "54") (name "unconnected-(S3-PSEL-Pad8)") (class "Default")
      (node (ref "S3") (pin "8") (pinfunction "PSEL_8") (pintype "input+no_connect"))
    )
    (net (code "55") (name "unconnected-(S3-PWM-Pad9)") (class "Default")
      (node (ref "S3") (pin "9") (pinfunction "PWM_9") (pintype "output+no_connect"))
    )
    (net (code "56") (name "unconnected-(S3-PWM_DIS-Pad5)") (class "Default")
      (node (ref "S3") (pin "5") (pinfunction "PWM_DIS_5") (pintype "input+no_connect"))
    )
    (net (code "57") (name "unconnected-(S3-RX-Pad2)") (class "Default")
      (node (ref "S3") (pin "2") (pinfunction "RX_2") (pintype "bidirectional+no_connect"))
    )
    (net (code "58") (name "unconnected-(U3-3V3_EN-Pad37)") (class "Default")
      (node (ref "U3") (pin "37") (pinfunction "3V3_EN_37") (pintype "input+no_connect"))
    )
    (net (code "59") (name "unconnected-(U3-GND-PadD2)") (class "Default")
      (node (ref "U3") (pin "D2") (pinfunction "GND_D2") (pintype "bidirectional+no_connect"))
    )
    (net (code "60") (name "unconnected-(U3-GP3-Pad5)") (class "Default")
      (node (ref "U3") (pin "5") (pinfunction "GP3_5") (pintype "bidirectional+no_connect"))
    )
    (net (code "61") (name "unconnected-(U3-GP6-Pad9)") (class "Default")
      (node (ref "U3") (pin "9") (pinfunction "GP6_9") (pintype "bidirectional+no_connect"))
    )
    (net (code "62") (name "unconnected-(U3-GP11-Pad15)") (class "Default")
      (node (ref "U3") (pin "15") (pinfunction "GP11_15") (pintype "bidirectional+no_connect"))
    )
    (net (code "63") (name "unconnected-(U3-GP13-Pad17)") (class "Default")
      (node (ref "U3") (pin "17") (pinfunction "GP13_17") (pintype "bidirectional+no_connect"))
    )
    (net (code "64") (name "unconnected-(U3-GP14-Pad19)") (class "Default")
      (node (ref "U3") (pin "19") (pinfunction "GP14_19") (pintype "bidirectional+no_connect"))
    )
    (net (code "65") (name "unconnected-(U3-SWCLK-PadD1)") (class "Default")
      (node (ref "U3") (pin "D1") (pinfunction "SWCLK_D1") (pintype "input+no_connect"))
    )
    (net (code "66") (name "unconnected-(U3-SWDIO-PadD3)") (class "Default")
      (node (ref "U3") (pin "D3") (pinfunction "SWDIO_D3") (pintype "bidirectional+no_connect"))
    )
    (net (code "67") (name "unconnected-(U3-TP1_GND-PadTP1)") (class "Default")
      (node (ref "U3") (pin "TP1") (pinfunction "TP1_GND_TP1") (pintype "power_in+no_connect"))
    )
    (net (code "68") (name "unconnected-(U3-TP2_USB_DM-PadTP2)") (class "Default")
      (node (ref "U3") (pin "TP2") (pinfunction "TP2_USB_DM_TP2") (pintype "bidirectional+no_connect"))
    )
    (net (code "69") (name "unconnected-(U3-TP3_USB_DP-PadTP3)") (class "Default")
      (node (ref "U3") (pin "TP3") (pinfunction "TP3_USB_DP_TP3") (pintype "bidirectional+no_connect"))
    )
    (net (code "70") (name "unconnected-(U3-TP4_GPIO23{slash}SMPS_PS-PadTP4)") (class "Default")
      (node (ref "U3") (pin "TP4") (pinfunction "TP4_GPIO23/SMPS_PS_TP4") (pintype "passive+no_connect"))
    )
    (net (code "71") (name "unconnected-(U3-TP5_GPIO25{slash}LED-PadTP5)") (class "Default")
      (node (ref "U3") (pin "TP5") (pinfunction "TP5_GPIO25/LED_TP5") (pintype "output+no_connect"))
    )
    (net (code "72") (name "unconnected-(U3-TP6_BOOTSEL-PadTP6)") (class "Default")
      (node (ref "U3") (pin "TP6") (pinfunction "TP6_BOOTSEL_TP6") (pintype "input+no_connect"))
    )
    (net (code "73") (name "unconnected-(U3-USB_SHIELD-PadA)") (class "Default")
      (node (ref "U3") (pin "A") (pinfunction "USB_SHIELD_A") (pintype "power_in+no_connect"))
    )
    (net (code "74") (name "unconnected-(U3-USB_SHIELD-PadB)") (class "Default")
      (node (ref "U3") (pin "B") (pinfunction "USB_SHIELD_B") (pintype "power_in+no_connect"))
    )
    (net (code "75") (name "unconnected-(U3-USB_SHIELD-PadC)") (class "Default")
      (node (ref "U3") (pin "C") (pinfunction "USB_SHIELD_C") (pintype "power_in+no_connect"))
    )
    (net (code "76") (name "unconnected-(U3-USB_SHIELD-PadD)") (class "Default")
      (node (ref "U3") (pin "D") (pinfunction "USB_SHIELD_D") (pintype "power_in+no_connect"))
    )
    (net (code "77") (name "unconnected-(U3-VBUS-Pad40)") (class "Default")
      (node (ref "U3") (pin "40") (pinfunction "VBUS_40") (pintype "power_in+no_connect"))
    )
    (net (code "78") (name "unconnected-(U3-~{RUN}-Pad30)") (class "Default")
      (node (ref "U3") (pin "30") (pinfunction "~{RUN}_30") (pintype "input+no_connect"))
    )
    (net (code "79") (name "unconnected-(U5-NC-Pad4)") (class "Default")
      (node (ref "U5") (pin "4") (pinfunction "NC_4") (pintype "passive+no_connect"))
    )
    (net (code "80") (name "unconnected-(U6-LNA_EN-Pad4)") (class "Default")
      (node (ref "U6") (pin "4") (pinfunction "LNA_EN_4") (pintype "input+no_connect"))
    )
    (net (code "81") (name "unconnected-(U6-SAFEBOOT-Pad3)") (class "Default")
      (node (ref "U6") (pin "3") (pinfunction "SAFEBOOT_3") (pintype "input+no_connect"))
    )
    (net (code "82") (name "unconnected-(U6-TIMEPULS-Pad6)") (class "Default")
      (node (ref "U6") (pin "6") (pinfunction "TIMEPULS_6") (pintype "input+no_connect"))
    )
  )
)
